# RK3566_DDR3.net
KiCad netlist of a schematic drawn in Altium Designer
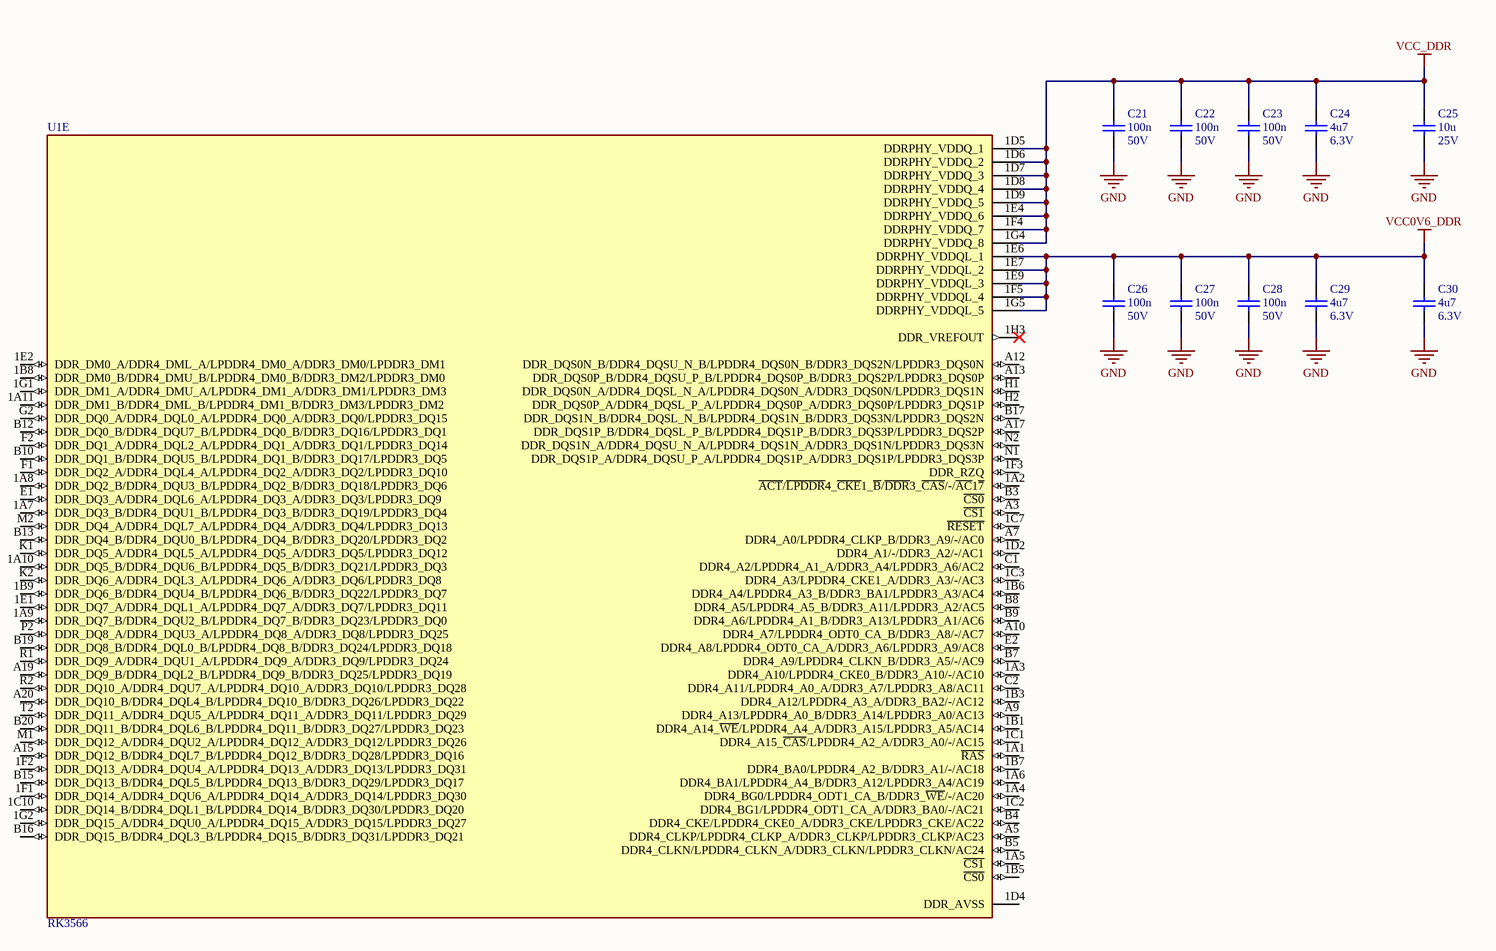
[diagram p0: RK3566_DDR3.SchDoc]

(export (version "E")
  (design (tool "Eeschema 10.0.6"))
  (components
    (comp (ref "C21")
      (value "100n")
      (description "CAP 100N 50V X7R 0402")
      (fields (field (name "VOLTAGE") "50V") (field (name "Comment") "GRM155R71H104KE14D"))
      (libsource (lib "PersonalAltiumLibrary") (part "GRM155R71H104KE14D"))
    )
    (comp (ref "C22")
      (value "100n")
      (description "CAP 100N 50V X7R 0402")
      (fields (field (name "VOLTAGE") "50V") (field (name "Comment") "GRM155R71H104KE14D"))
      (libsource (lib "PersonalAltiumLibrary") (part "GRM155R71H104KE14D"))
    )
    (comp (ref "C23")
      (value "100n")
      (description "CAP 100N 50V X7R 0402")
      (fields (field (name "VOLTAGE") "50V") (field (name "Comment") "GRM155R71H104KE14D"))
      (libsource (lib "PersonalAltiumLibrary") (part "GRM155R71H104KE14D"))
    )
    (comp (ref "C24")
      (value "4u7")
      (description "CAP 4.7U 6.3V X5R 0402")
      (fields (field (name "VOLTAGE") "6.3V") (field (name "Comment") "GRM155R60J475ME47D"))
      (libsource (lib "PersonalAltiumLibrary") (part "GRM155R60J475ME47D"))
    )
    (comp (ref "C25")
      (value "10u")
      (description "CAP 10U 25V X5R 0603")
      (fields (field (name "VOLTAGE") "25V") (field (name "Comment") "GRM188R61E106MA73D"))
      (libsource (lib "PersonalAltiumLibrary") (part "GRM188R61E106MA73D"))
    )
    (comp (ref "C26")
      (value "100n")
      (description "CAP 100N 50V X7R 0402")
      (fields (field (name "VOLTAGE") "50V") (field (name "Comment") "GRM155R71H104KE14D"))
      (libsource (lib "PersonalAltiumLibrary") (part "GRM155R71H104KE14D"))
    )
    (comp (ref "C27")
      (value "100n")
      (description "CAP 100N 50V X7R 0402")
      (fields (field (name "VOLTAGE") "50V") (field (name "Comment") "GRM155R71H104KE14D"))
      (libsource (lib "PersonalAltiumLibrary") (part "GRM155R71H104KE14D"))
    )
    (comp (ref "C28")
      (value "100n")
      (description "CAP 100N 50V X7R 0402")
      (fields (field (name "VOLTAGE") "50V") (field (name "Comment") "GRM155R71H104KE14D"))
      (libsource (lib "PersonalAltiumLibrary") (part "GRM155R71H104KE14D"))
    )
    (comp (ref "C29")
      (value "4u7")
      (description "CAP 4.7U 6.3V X5R 0402")
      (fields (field (name "VOLTAGE") "6.3V") (field (name "Comment") "GRM155R60J475ME47D"))
      (libsource (lib "PersonalAltiumLibrary") (part "GRM155R60J475ME47D"))
    )
    (comp (ref "C30")
      (value "4u7")
      (description "CAP 4.7U 6.3V X5R 0402")
      (fields (field (name "VOLTAGE") "6.3V") (field (name "Comment") "GRM155R60J475ME47D"))
      (libsource (lib "PersonalAltiumLibrary") (part "GRM155R60J475ME47D"))
    )
    (comp (ref "U1")
      (value "RK3566")
      (footprint "RK3566")
      (description "high-performance and low-power quad-core application processor")
      (fields (field (name "MF") "Fuzhou Rockchip Electronics Co"))
      (libsource (lib "PersonalAltiumLibrary") (part "RK3566"))
    )
  )
  (nets
    (net (code "1") (name "GND") (class "Default")
      (node (ref "C21") (pin "2") (pinfunction "2_2") (pintype "passive"))
      (node (ref "C22") (pin "2") (pinfunction "2_2") (pintype "passive"))
      (node (ref "C23") (pin "2") (pinfunction "2_2") (pintype "passive"))
      (node (ref "C24") (pin "2") (pinfunction "2_2") (pintype "passive"))
      (node (ref "C25") (pin "2") (pinfunction "2_2") (pintype "passive"))
      (node (ref "C26") (pin "2") (pinfunction "2_2") (pintype "passive"))
      (node (ref "C27") (pin "2") (pinfunction "2_2") (pintype "passive"))
      (node (ref "C28") (pin "2") (pinfunction "2_2") (pintype "passive"))
      (node (ref "C29") (pin "2") (pinfunction "2_2") (pintype "passive"))
      (node (ref "C30") (pin "2") (pinfunction "2_2") (pintype "passive"))
    )
    (net (code "2") (name "VCC0V6_DDR") (class "Default")
      (node (ref "C26") (pin "1") (pinfunction "1_1") (pintype "passive"))
      (node (ref "C27") (pin "1") (pinfunction "1_1") (pintype "passive"))
      (node (ref "C28") (pin "1") (pinfunction "1_1") (pintype "passive"))
      (node (ref "C29") (pin "1") (pinfunction "1_1") (pintype "passive"))
      (node (ref "C30") (pin "1") (pinfunction "1_1") (pintype "passive"))
      (node (ref "U1") (pin "1E6") (pinfunction "DDRPHY_VDDQL_1_1E6") (pintype "power_in"))
      (node (ref "U1") (pin "1E7") (pinfunction "DDRPHY_VDDQL_2_1E7") (pintype "power_in"))
      (node (ref "U1") (pin "1E9") (pinfunction "DDRPHY_VDDQL_3_1E9") (pintype "power_in"))
      (node (ref "U1") (pin "1F5") (pinfunction "DDRPHY_VDDQL_4_1F5") (pintype "power_in"))
      (node (ref "U1") (pin "1G5") (pinfunction "DDRPHY_VDDQL_5_1G5") (pintype "power_in"))
    )
    (net (code "3") (name "VCC_DDR") (class "Default")
      (node (ref "C21") (pin "1") (pinfunction "1_1") (pintype "passive"))
      (node (ref "C22") (pin "1") (pinfunction "1_1") (pintype "passive"))
      (node (ref "C23") (pin "1") (pinfunction "1_1") (pintype "passive"))
      (node (ref "C24") (pin "1") (pinfunction "1_1") (pintype "passive"))
      (node (ref "C25") (pin "1") (pinfunction "1_1") (pintype "passive"))
      (node (ref "U1") (pin "1D5") (pinfunction "DDRPHY_VDDQ_1_1D5") (pintype "power_in"))
      (node (ref "U1") (pin "1D6") (pinfunction "DDRPHY_VDDQ_2_1D6") (pintype "power_in"))
      (node (ref "U1") (pin "1D7") (pinfunction "DDRPHY_VDDQ_3_1D7") (pintype "power_in"))
      (node (ref "U1") (pin "1D8") (pinfunction "DDRPHY_VDDQ_4_1D8") (pintype "power_in"))
      (node (ref "U1") (pin "1D9") (pinfunction "DDRPHY_VDDQ_5_1D9") (pintype "power_in"))
      (node (ref "U1") (pin "1E4") (pinfunction "DDRPHY_VDDQ_6_1E4") (pintype "power_in"))
      (node (ref "U1") (pin "1F4") (pinfunction "DDRPHY_VDDQ_7_1F4") (pintype "power_in"))
      (node (ref "U1") (pin "1G4") (pinfunction "DDRPHY_VDDQ_8_1G4") (pintype "power_in"))
    )
    (net (code "4") (name "unconnected-(U1E-DDR4_A0{slash}LPDDR4_CLKP_B{slash}DDR3_A9{slash}-{slash}AC0-PadA7)") (class "Default")
      (node (ref "U1") (pin "A7") (pinfunction "DDR4_A0/LPDDR4_CLKP_B/DDR3_A9/-/AC0_A7") (pintype "bidirectional"))
    )
    (net (code "5") (name "unconnected-(U1E-DDR4_A1{slash}-{slash}DDR3_A2{slash}-{slash}AC1-Pad1D2)") (class "Default")
      (node (ref "U1") (pin "1D2") (pinfunction "DDR4_A1/-/DDR3_A2/-/AC1_1D2") (pintype "bidirectional"))
    )
    (net (code "6") (name "unconnected-(U1E-DDR4_A2{slash}LPDDR4_A1_A{slash}DDR3_A4{slash}LPDDR3_A6{slash}AC2-PadC1)") (class "Default")
      (node (ref "U1") (pin "C1") (pinfunction "DDR4_A2/LPDDR4_A1_A/DDR3_A4/LPDDR3_A6/AC2_C1") (pintype "bidirectional"))
    )
    (net (code "7") (name "unconnected-(U1E-DDR4_A3{slash}LPDDR4_CKE1_A{slash}DDR3_A3{slash}-{slash}AC3-Pad1C3)") (class "Default")
      (node (ref "U1") (pin "1C3") (pinfunction "DDR4_A3/LPDDR4_CKE1_A/DDR3_A3/-/AC3_1C3") (pintype "bidirectional"))
    )
    (net (code "8") (name "unconnected-(U1E-DDR4_A4{slash}LPDDR4_A3_B{slash}DDR3_BA1{slash}LPDDR3_A3{slash}AC4-Pad1B6)") (class "Default")
      (node (ref "U1") (pin "1B6") (pinfunction "DDR4_A4/LPDDR4_A3_B/DDR3_BA1/LPDDR3_A3/AC4_1B6") (pintype "bidirectional"))
    )
    (net (code "9") (name "unconnected-(U1E-DDR4_A5{slash}LPDDR4_A5_B{slash}DDR3_A11{slash}LPDDR3_A2{slash}AC5-PadB8)") (class "Default")
      (node (ref "U1") (pin "B8") (pinfunction "DDR4_A5/LPDDR4_A5_B/DDR3_A11/LPDDR3_A2/AC5_B8") (pintype "bidirectional"))
    )
    (net (code "10") (name "unconnected-(U1E-DDR4_A6{slash}LPDDR4_A1_B{slash}DDR3_A13{slash}LPDDR3_A1{slash}AC6-PadB9)") (class "Default")
      (node (ref "U1") (pin "B9") (pinfunction "DDR4_A6/LPDDR4_A1_B/DDR3_A13/LPDDR3_A1/AC6_B9") (pintype "bidirectional"))
    )
    (net (code "11") (name "unconnected-(U1E-DDR4_A7{slash}LPDDR4_ODT0_CA_B{slash}DDR3_A8{slash}-{slash}AC7-PadA10)") (class "Default")
      (node (ref "U1") (pin "A10") (pinfunction "DDR4_A7/LPDDR4_ODT0_CA_B/DDR3_A8/-/AC7_A10") (pintype "bidirectional"))
    )
    (net (code "12") (name "unconnected-(U1E-DDR4_A8{slash}LPDDR4_ODT0_CA_A{slash}DDR3_A6{slash}LPDDR3_A9{slash}AC8-PadE2)") (class "Default")
      (node (ref "U1") (pin "E2") (pinfunction "DDR4_A8/LPDDR4_ODT0_CA_A/DDR3_A6/LPDDR3_A9/AC8_E2") (pintype "bidirectional"))
    )
    (net (code "13") (name "unconnected-(U1E-DDR4_A9{slash}LPDDR4_CLKN_B{slash}DDR3_A5{slash}-{slash}AC9-PadB7)") (class "Default")
      (node (ref "U1") (pin "B7") (pinfunction "DDR4_A9/LPDDR4_CLKN_B/DDR3_A5/-/AC9_B7") (pintype "bidirectional"))
    )
    (net (code "14") (name "unconnected-(U1E-DDR4_A10{slash}LPDDR4_CKE0_B{slash}DDR3_A10{slash}-{slash}AC10-Pad1A3)") (class "Default")
      (node (ref "U1") (pin "1A3") (pinfunction "DDR4_A10/LPDDR4_CKE0_B/DDR3_A10/-/AC10_1A3") (pintype "bidirectional"))
    )
    (net (code "15") (name "unconnected-(U1E-DDR4_A11{slash}LPDDR4_A0_A{slash}DDR3_A7{slash}LPDDR3_A8{slash}AC11-PadC2)") (class "Default")
      (node (ref "U1") (pin "C2") (pinfunction "DDR4_A11/LPDDR4_A0_A/DDR3_A7/LPDDR3_A8/AC11_C2") (pintype "bidirectional"))
    )
    (net (code "16") (name "unconnected-(U1E-DDR4_A12{slash}LPDDR4_A3_A{slash}DDR3_BA2{slash}-{slash}AC12-Pad1B3)") (class "Default")
      (node (ref "U1") (pin "1B3") (pinfunction "DDR4_A12/LPDDR4_A3_A/DDR3_BA2/-/AC12_1B3") (pintype "bidirectional"))
    )
    (net (code "17") (name "unconnected-(U1E-DDR4_A13{slash}LPDDR4_A0_B{slash}DDR3_A14{slash}LPDDR3_A0{slash}AC13-PadA9)") (class "Default")
      (node (ref "U1") (pin "A9") (pinfunction "DDR4_A13/LPDDR4_A0_B/DDR3_A14/LPDDR3_A0/AC13_A9") (pintype "bidirectional"))
    )
    (net (code "18") (name "unconnected-(U1E-DDR4_A14_~{WE}{slash}LPDDR4_A4_A{slash}DDR3_A15{slash}LPDDR3_A5{slash}AC14-Pad1B1)") (class "Default")
      (node (ref "U1") (pin "1B1") (pinfunction "DDR4_A14_~{WE}/LPDDR4_A4_A/DDR3_A15/LPDDR3_A5/AC14_1B1") (pintype "bidirectional"))
    )
    (net (code "19") (name "unconnected-(U1E-DDR4_A15_~{CAS}{slash}LPDDR4_A2_A{slash}DDR3_A0{slash}-{slash}AC15-Pad1C1)") (class "Default")
      (node (ref "U1") (pin "1C1") (pinfunction "DDR4_A15_~{CAS}/LPDDR4_A2_A/DDR3_A0/-/AC15_1C1") (pintype "bidirectional"))
    )
    (net (code "20") (name "unconnected-(U1E-DDR4_BA0{slash}LPDDR4_A2_B{slash}DDR3_A1{slash}-{slash}AC18-Pad1B7)") (class "Default")
      (node (ref "U1") (pin "1B7") (pinfunction "DDR4_BA0/LPDDR4_A2_B/DDR3_A1/-/AC18_1B7") (pintype "bidirectional"))
    )
    (net (code "21") (name "unconnected-(U1E-DDR4_BA1{slash}LPDDR4_A4_B{slash}DDR3_A12{slash}LPDDR3_A4{slash}AC19-Pad1A6)") (class "Default")
      (node (ref "U1") (pin "1A6") (pinfunction "DDR4_BA1/LPDDR4_A4_B/DDR3_A12/LPDDR3_A4/AC19_1A6") (pintype "bidirectional"))
    )
    (net (code "22") (name "unconnected-(U1E-DDR4_BG0{slash}LPDDR4_ODT1_CA_B{slash}DDR3_~{WE}{slash}-{slash}AC20-Pad1A4)") (class "Default")
      (node (ref "U1") (pin "1A4") (pinfunction "DDR4_BG0/LPDDR4_ODT1_CA_B/DDR3_~{WE}/-/AC20_1A4") (pintype "bidirectional"))
    )
    (net (code "23") (name "unconnected-(U1E-DDR4_BG1{slash}LPDDR4_ODT1_CA_A{slash}DDR3_BA0{slash}-{slash}AC21-Pad1C2)") (class "Default")
      (node (ref "U1") (pin "1C2") (pinfunction "DDR4_BG1/LPDDR4_ODT1_CA_A/DDR3_BA0/-/AC21_1C2") (pintype "bidirectional"))
    )
    (net (code "24") (name "unconnected-(U1E-DDR4_CKE{slash}LPDDR4_CKE0_A{slash}DDR3_CKE{slash}LPDDR3_CKE{slash}AC22-PadB4)") (class "Default")
      (node (ref "U1") (pin "B4") (pinfunction "DDR4_CKE/LPDDR4_CKE0_A/DDR3_CKE/LPDDR3_CKE/AC22_B4") (pintype "bidirectional"))
    )
    (net (code "25") (name "unconnected-(U1E-DDR4_CLKN{slash}LPDDR4_CLKN_A{slash}DDR3_CLKN{slash}LPDDR3_CLKN{slash}AC24-PadB5)") (class "Default")
      (node (ref "U1") (pin "B5") (pinfunction "DDR4_CLKN/LPDDR4_CLKN_A/DDR3_CLKN/LPDDR3_CLKN/AC24_B5") (pintype "bidirectional"))
    )
    (net (code "26") (name "unconnected-(U1E-DDR4_CLKP{slash}LPDDR4_CLKP_A{slash}DDR3_CLKP{slash}LPDDR3_CLKP{slash}AC23-PadA5)") (class "Default")
      (node (ref "U1") (pin "A5") (pinfunction "DDR4_CLKP/LPDDR4_CLKP_A/DDR3_CLKP/LPDDR3_CLKP/AC23_A5") (pintype "bidirectional"))
    )
    (net (code "27") (name "unconnected-(U1E-DDR_AVSS-Pad1D4)") (class "Default")
      (node (ref "U1") (pin "1D4") (pinfunction "DDR_AVSS_1D4") (pintype "power_in"))
    )
    (net (code "28") (name "unconnected-(U1E-DDR_DM0_A{slash}DDR4_DML_A{slash}LPDDR4_DM0_A{slash}DDR3_DM0{slash}LPDDR3_DM1-Pad1E2)") (class "Default")
      (node (ref "U1") (pin "1E2") (pinfunction "DDR_DM0_A/DDR4_DML_A/LPDDR4_DM0_A/DDR3_DM0/LPDDR3_DM1_1E2") (pintype "bidirectional"))
    )
    (net (code "29") (name "unconnected-(U1E-DDR_DM0_B{slash}DDR4_DMU_B{slash}LPDDR4_DM0_B{slash}DDR3_DM2{slash}LPDDR3_DM0-Pad1B8)") (class "Default")
      (node (ref "U1") (pin "1B8") (pinfunction "DDR_DM0_B/DDR4_DMU_B/LPDDR4_DM0_B/DDR3_DM2/LPDDR3_DM0_1B8") (pintype "bidirectional"))
    )
    (net (code "30") (name "unconnected-(U1E-DDR_DM1_A{slash}DDR4_DMU_A{slash}LPDDR4_DM1_A{slash}DDR3_DM1{slash}LPDDR3_DM3-Pad1G1)") (class "Default")
      (node (ref "U1") (pin "1G1") (pinfunction "DDR_DM1_A/DDR4_DMU_A/LPDDR4_DM1_A/DDR3_DM1/LPDDR3_DM3_1G1") (pintype "bidirectional"))
    )
    (net (code "31") (name "unconnected-(U1E-DDR_DM1_B{slash}DDR4_DML_B{slash}LPDDR4_DM1_B{slash}DDR3_DM3{slash}LPDDR3_DM2-Pad1A11)") (class "Default")
      (node (ref "U1") (pin "1A11") (pinfunction "DDR_DM1_B/DDR4_DML_B/LPDDR4_DM1_B/DDR3_DM3/LPDDR3_DM2_1A11") (pintype "bidirectional"))
    )
    (net (code "32") (name "unconnected-(U1E-DDR_DQ0_A{slash}DDR4_DQL0_A{slash}LPDDR4_DQ0_A{slash}DDR3_DQ0{slash}LPDDR3_DQ15-PadG2)") (class "Default")
      (node (ref "U1") (pin "G2") (pinfunction "DDR_DQ0_A/DDR4_DQL0_A/LPDDR4_DQ0_A/DDR3_DQ0/LPDDR3_DQ15_G2") (pintype "bidirectional"))
    )
    (net (code "33") (name "unconnected-(U1E-DDR_DQ0_B{slash}DDR4_DQU7_B{slash}LPDDR4_DQ0_B{slash}DDR3_DQ16{slash}LPDDR3_DQ1-PadB12)") (class "Default")
      (node (ref "U1") (pin "B12") (pinfunction "DDR_DQ0_B/DDR4_DQU7_B/LPDDR4_DQ0_B/DDR3_DQ16/LPDDR3_DQ1_B12") (pintype "bidirectional"))
    )
    (net (code "34") (name "unconnected-(U1E-DDR_DQ1_A{slash}DDR4_DQL2_A{slash}LPDDR4_DQ1_A{slash}DDR3_DQ1{slash}LPDDR3_DQ14-PadF2)") (class "Default")
      (node (ref "U1") (pin "F2") (pinfunction "DDR_DQ1_A/DDR4_DQL2_A/LPDDR4_DQ1_A/DDR3_DQ1/LPDDR3_DQ14_F2") (pintype "bidirectional"))
    )
    (net (code "35") (name "unconnected-(U1E-DDR_DQ1_B{slash}DDR4_DQU5_B{slash}LPDDR4_DQ1_B{slash}DDR3_DQ17{slash}LPDDR3_DQ5-PadB10)") (class "Default")
      (node (ref "U1") (pin "B10") (pinfunction "DDR_DQ1_B/DDR4_DQU5_B/LPDDR4_DQ1_B/DDR3_DQ17/LPDDR3_DQ5_B10") (pintype "bidirectional"))
    )
    (net (code "36") (name "unconnected-(U1E-DDR_DQ2_A{slash}DDR4_DQL4_A{slash}LPDDR4_DQ2_A{slash}DDR3_DQ2{slash}LPDDR3_DQ10-PadF1)") (class "Default")
      (node (ref "U1") (pin "F1") (pinfunction "DDR_DQ2_A/DDR4_DQL4_A/LPDDR4_DQ2_A/DDR3_DQ2/LPDDR3_DQ10_F1") (pintype "bidirectional"))
    )
    (net (code "37") (name "unconnected-(U1E-DDR_DQ2_B{slash}DDR4_DQU3_B{slash}LPDDR4_DQ2_B{slash}DDR3_DQ18{slash}LPDDR3_DQ6-Pad1A8)") (class "Default")
      (node (ref "U1") (pin "1A8") (pinfunction "DDR_DQ2_B/DDR4_DQU3_B/LPDDR4_DQ2_B/DDR3_DQ18/LPDDR3_DQ6_1A8") (pintype "bidirectional"))
    )
    (net (code "38") (name "unconnected-(U1E-DDR_DQ3_A{slash}DDR4_DQL6_A{slash}LPDDR4_DQ3_A{slash}DDR3_DQ3{slash}LPDDR3_DQ9-PadE1)") (class "Default")
      (node (ref "U1") (pin "E1") (pinfunction "DDR_DQ3_A/DDR4_DQL6_A/LPDDR4_DQ3_A/DDR3_DQ3/LPDDR3_DQ9_E1") (pintype "bidirectional"))
    )
    (net (code "39") (name "unconnected-(U1E-DDR_DQ3_B{slash}DDR4_DQU1_B{slash}LPDDR4_DQ3_B{slash}DDR3_DQ19{slash}LPDDR3_DQ4-Pad1A7)") (class "Default")
      (node (ref "U1") (pin "1A7") (pinfunction "DDR_DQ3_B/DDR4_DQU1_B/LPDDR4_DQ3_B/DDR3_DQ19/LPDDR3_DQ4_1A7") (pintype "bidirectional"))
    )
    (net (code "40") (name "unconnected-(U1E-DDR_DQ4_A{slash}DDR4_DQL7_A{slash}LPDDR4_DQ4_A{slash}DDR3_DQ4{slash}LPDDR3_DQ13-PadM2)") (class "Default")
      (node (ref "U1") (pin "M2") (pinfunction "DDR_DQ4_A/DDR4_DQL7_A/LPDDR4_DQ4_A/DDR3_DQ4/LPDDR3_DQ13_M2") (pintype "bidirectional"))
    )
    (net (code "41") (name "unconnected-(U1E-DDR_DQ4_B{slash}DDR4_DQU0_B{slash}LPDDR4_DQ4_B{slash}DDR3_DQ20{slash}LPDDR3_DQ2-PadB13)") (class "Default")
      (node (ref "U1") (pin "B13") (pinfunction "DDR_DQ4_B/DDR4_DQU0_B/LPDDR4_DQ4_B/DDR3_DQ20/LPDDR3_DQ2_B13") (pintype "bidirectional"))
    )
    (net (code "42") (name "unconnected-(U1E-DDR_DQ5_A{slash}DDR4_DQL5_A{slash}LPDDR4_DQ5_A{slash}DDR3_DQ5{slash}LPDDR3_DQ12-PadK1)") (class "Default")
      (node (ref "U1") (pin "K1") (pinfunction "DDR_DQ5_A/DDR4_DQL5_A/LPDDR4_DQ5_A/DDR3_DQ5/LPDDR3_DQ12_K1") (pintype "bidirectional"))
    )
    (net (code "43") (name "unconnected-(U1E-DDR_DQ5_B{slash}DDR4_DQU6_B{slash}LPDDR4_DQ5_B{slash}DDR3_DQ21{slash}LPDDR3_DQ3-Pad1A10)") (class "Default")
      (node (ref "U1") (pin "1A10") (pinfunction "DDR_DQ5_B/DDR4_DQU6_B/LPDDR4_DQ5_B/DDR3_DQ21/LPDDR3_DQ3_1A10") (pintype "bidirectional"))
    )
    (net (code "44") (name "unconnected-(U1E-DDR_DQ6_A{slash}DDR4_DQL3_A{slash}LPDDR4_DQ6_A{slash}DDR3_DQ6{slash}LPDDR3_DQ8-PadK2)") (class "Default")
      (node (ref "U1") (pin "K2") (pinfunction "DDR_DQ6_A/DDR4_DQL3_A/LPDDR4_DQ6_A/DDR3_DQ6/LPDDR3_DQ8_K2") (pintype "bidirectional"))
    )
    (net (code "45") (name "unconnected-(U1E-DDR_DQ6_B{slash}DDR4_DQU4_B{slash}LPDDR4_DQ6_B{slash}DDR3_DQ22{slash}LPDDR3_DQ7-Pad1B9)") (class "Default")
      (node (ref "U1") (pin "1B9") (pinfunction "DDR_DQ6_B/DDR4_DQU4_B/LPDDR4_DQ6_B/DDR3_DQ22/LPDDR3_DQ7_1B9") (pintype "bidirectional"))
    )
    (net (code "46") (name "unconnected-(U1E-DDR_DQ7_A{slash}DDR4_DQL1_A{slash}LPDDR4_DQ7_A{slash}DDR3_DQ7{slash}LPDDR3_DQ11-Pad1E1)") (class "Default")
      (node (ref "U1") (pin "1E1") (pinfunction "DDR_DQ7_A/DDR4_DQL1_A/LPDDR4_DQ7_A/DDR3_DQ7/LPDDR3_DQ11_1E1") (pintype "bidirectional"))
    )
    (net (code "47") (name "unconnected-(U1E-DDR_DQ7_B{slash}DDR4_DQU2_B{slash}LPDDR4_DQ7_B{slash}DDR3_DQ23{slash}LPDDR3_DQ0-Pad1A9)") (class "Default")
      (node (ref "U1") (pin "1A9") (pinfunction "DDR_DQ7_B/DDR4_DQU2_B/LPDDR4_DQ7_B/DDR3_DQ23/LPDDR3_DQ0_1A9") (pintype "bidirectional"))
    )
    (net (code "48") (name "unconnected-(U1E-DDR_DQ8_A{slash}DDR4_DQU3_A{slash}LPDDR4_DQ8_A{slash}DDR3_DQ8{slash}LPDDR3_DQ25-PadP2)") (class "Default")
      (node (ref "U1") (pin "P2") (pinfunction "DDR_DQ8_A/DDR4_DQU3_A/LPDDR4_DQ8_A/DDR3_DQ8/LPDDR3_DQ25_P2") (pintype "bidirectional"))
    )
    (net (code "49") (name "unconnected-(U1E-DDR_DQ8_B{slash}DDR4_DQL0_B{slash}LPDDR4_DQ8_B{slash}DDR3_DQ24{slash}LPDDR3_DQ18-PadB19)") (class "Default")
      (node (ref "U1") (pin "B19") (pinfunction "DDR_DQ8_B/DDR4_DQL0_B/LPDDR4_DQ8_B/DDR3_DQ24/LPDDR3_DQ18_B19") (pintype "bidirectional"))
    )
    (net (code "50") (name "unconnected-(U1E-DDR_DQ9_A{slash}DDR4_DQU1_A{slash}LPDDR4_DQ9_A{slash}DDR3_DQ9{slash}LPDDR3_DQ24-PadR1)") (class "Default")
      (node (ref "U1") (pin "R1") (pinfunction "DDR_DQ9_A/DDR4_DQU1_A/LPDDR4_DQ9_A/DDR3_DQ9/LPDDR3_DQ24_R1") (pintype "bidirectional"))
    )
    (net (code "51") (name "unconnected-(U1E-DDR_DQ9_B{slash}DDR4_DQL2_B{slash}LPDDR4_DQ9_B{slash}DDR3_DQ25{slash}LPDDR3_DQ19-PadA19)") (class "Default")
      (node (ref "U1") (pin "A19") (pinfunction "DDR_DQ9_B/DDR4_DQL2_B/LPDDR4_DQ9_B/DDR3_DQ25/LPDDR3_DQ19_A19") (pintype "bidirectional"))
    )
    (net (code "52") (name "unconnected-(U1E-DDR_DQ10_A{slash}DDR4_DQU7_A{slash}LPDDR4_DQ10_A{slash}DDR3_DQ10{slash}LPDDR3_DQ28-PadR2)") (class "Default")
      (node (ref "U1") (pin "R2") (pinfunction "DDR_DQ10_A/DDR4_DQU7_A/LPDDR4_DQ10_A/DDR3_DQ10/LPDDR3_DQ28_R2") (pintype "bidirectional"))
    )
    (net (code "53") (name "unconnected-(U1E-DDR_DQ10_B{slash}DDR4_DQL4_B{slash}LPDDR4_DQ10_B{slash}DDR3_DQ26{slash}LPDDR3_DQ22-PadA20)") (class "Default")
      (node (ref "U1") (pin "A20") (pinfunction "DDR_DQ10_B/DDR4_DQL4_B/LPDDR4_DQ10_B/DDR3_DQ26/LPDDR3_DQ22_A20") (pintype "bidirectional"))
    )
    (net (code "54") (name "unconnected-(U1E-DDR_DQ11_A{slash}DDR4_DQU5_A{slash}LPDDR4_DQ11_A{slash}DDR3_DQ11{slash}LPDDR3_DQ29-PadT2)") (class "Default")
      (node (ref "U1") (pin "T2") (pinfunction "DDR_DQ11_A/DDR4_DQU5_A/LPDDR4_DQ11_A/DDR3_DQ11/LPDDR3_DQ29_T2") (pintype "bidirectional"))
    )
    (net (code "55") (name "unconnected-(U1E-DDR_DQ11_B{slash}DDR4_DQL6_B{slash}LPDDR4_DQ11_B{slash}DDR3_DQ27{slash}LPDDR3_DQ23-PadB20)") (class "Default")
      (node (ref "U1") (pin "B20") (pinfunction "DDR_DQ11_B/DDR4_DQL6_B/LPDDR4_DQ11_B/DDR3_DQ27/LPDDR3_DQ23_B20") (pintype "bidirectional"))
    )
    (net (code "56") (name "unconnected-(U1E-DDR_DQ12_A{slash}DDR4_DQU2_A{slash}LPDDR4_DQ12_A{slash}DDR3_DQ12{slash}LPDDR3_DQ26-PadM1)") (class "Default")
      (node (ref "U1") (pin "M1") (pinfunction "DDR_DQ12_A/DDR4_DQU2_A/LPDDR4_DQ12_A/DDR3_DQ12/LPDDR3_DQ26_M1") (pintype "bidirectional"))
    )
    (net (code "57") (name "unconnected-(U1E-DDR_DQ12_B{slash}DDR4_DQL7_B{slash}LPDDR4_DQ12_B{slash}DDR3_DQ28{slash}LPDDR3_DQ16-PadA15)") (class "Default")
      (node (ref "U1") (pin "A15") (pinfunction "DDR_DQ12_B/DDR4_DQL7_B/LPDDR4_DQ12_B/DDR3_DQ28/LPDDR3_DQ16_A15") (pintype "bidirectional"))
    )
    (net (code "58") (name "unconnected-(U1E-DDR_DQ13_A{slash}DDR4_DQU4_A{slash}LPDDR4_DQ13_A{slash}DDR3_DQ13{slash}LPDDR3_DQ31-Pad1F2)") (class "Default")
      (node (ref "U1") (pin "1F2") (pinfunction "DDR_DQ13_A/DDR4_DQU4_A/LPDDR4_DQ13_A/DDR3_DQ13/LPDDR3_DQ31_1F2") (pintype "bidirectional"))
    )
    (net (code "59") (name "unconnected-(U1E-DDR_DQ13_B{slash}DDR4_DQL5_B{slash}LPDDR4_DQ13_B{slash}DDR3_DQ29{slash}LPDDR3_DQ17-PadB15)") (class "Default")
      (node (ref "U1") (pin "B15") (pinfunction "DDR_DQ13_B/DDR4_DQL5_B/LPDDR4_DQ13_B/DDR3_DQ29/LPDDR3_DQ17_B15") (pintype "bidirectional"))
    )
    (net (code "60") (name "unconnected-(U1E-DDR_DQ14_A{slash}DDR4_DQU6_A{slash}LPDDR4_DQ14_A{slash}DDR3_DQ14{slash}LPDDR3_DQ30-Pad1F1)") (class "Default")
      (node (ref "U1") (pin "1F1") (pinfunction "DDR_DQ14_A/DDR4_DQU6_A/LPDDR4_DQ14_A/DDR3_DQ14/LPDDR3_DQ30_1F1") (pintype "bidirectional"))
    )
    (net (code "61") (name "unconnected-(U1E-DDR_DQ14_B{slash}DDR4_DQL1_B{slash}LPDDR4_DQ14_B{slash}DDR3_DQ30{slash}LPDDR3_DQ20-Pad1C10)") (class "Default")
      (node (ref "U1") (pin "1C10") (pinfunction "DDR_DQ14_B/DDR4_DQL1_B/LPDDR4_DQ14_B/DDR3_DQ30/LPDDR3_DQ20_1C10") (pintype "bidirectional"))
    )
    (net (code "62") (name "unconnected-(U1E-DDR_DQ15_A{slash}DDR4_DQU0_A{slash}LPDDR4_DQ15_A{slash}DDR3_DQ15{slash}LPDDR3_DQ27-Pad1G2)") (class "Default")
      (node (ref "U1") (pin "1G2") (pinfunction "DDR_DQ15_A/DDR4_DQU0_A/LPDDR4_DQ15_A/DDR3_DQ15/LPDDR3_DQ27_1G2") (pintype "bidirectional"))
    )
    (net (code "63") (name "unconnected-(U1E-DDR_DQ15_B{slash}DDR4_DQL3_B{slash}LPDDR4_DQ15_B{slash}DDR3_DQ31{slash}LPDDR3_DQ21-PadB16)") (class "Default")
      (node (ref "U1") (pin "B16") (pinfunction "DDR_DQ15_B/DDR4_DQL3_B/LPDDR4_DQ15_B/DDR3_DQ31/LPDDR3_DQ21_B16") (pintype "bidirectional"))
    )
    (net (code "64") (name "unconnected-(U1E-DDR_DQS0N_A{slash}DDR4_DQSL_N_A{slash}LPDDR4_DQS0N_A{slash}DDR3_DQS0N{slash}LPDDR3_DQS1N-PadH1)") (class "Default")
      (node (ref "U1") (pin "H1") (pinfunction "DDR_DQS0N_A/DDR4_DQSL_N_A/LPDDR4_DQS0N_A/DDR3_DQS0N/LPDDR3_DQS1N_H1") (pintype "bidirectional"))
    )
    (net (code "65") (name "unconnected-(U1E-DDR_DQS0N_B{slash}DDR4_DQSU_N_B{slash}LPDDR4_DQS0N_B{slash}DDR3_DQS2N{slash}LPDDR3_DQS0N-PadA12)") (class "Default")
      (node (ref "U1") (pin "A12") (pinfunction "DDR_DQS0N_B/DDR4_DQSU_N_B/LPDDR4_DQS0N_B/DDR3_DQS2N/LPDDR3_DQS0N_A12") (pintype "bidirectional"))
    )
    (net (code "66") (name "unconnected-(U1E-DDR_DQS0P_A{slash}DDR4_DQSL_P_A{slash}LPDDR4_DQS0P_A{slash}DDR3_DQS0P{slash}LPDDR3_DQS1P-PadH2)") (class "Default")
      (node (ref "U1") (pin "H2") (pinfunction "DDR_DQS0P_A/DDR4_DQSL_P_A/LPDDR4_DQS0P_A/DDR3_DQS0P/LPDDR3_DQS1P_H2") (pintype "bidirectional"))
    )
    (net (code "67") (name "unconnected-(U1E-DDR_DQS0P_B{slash}DDR4_DQSU_P_B{slash}LPDDR4_DQS0P_B{slash}DDR3_DQS2P{slash}LPDDR3_DQS0P-PadA13)") (class "Default")
      (node (ref "U1") (pin "A13") (pinfunction "DDR_DQS0P_B/DDR4_DQSU_P_B/LPDDR4_DQS0P_B/DDR3_DQS2P/LPDDR3_DQS0P_A13") (pintype "bidirectional"))
    )
    (net (code "68") (name "unconnected-(U1E-DDR_DQS1N_A{slash}DDR4_DQSU_N_A{slash}LPDDR4_DQS1N_A{slash}DDR3_DQS1N{slash}LPDDR3_DQS3N-PadN2)") (class "Default")
      (node (ref "U1") (pin "N2") (pinfunction "DDR_DQS1N_A/DDR4_DQSU_N_A/LPDDR4_DQS1N_A/DDR3_DQS1N/LPDDR3_DQS3N_N2") (pintype "bidirectional"))
    )
    (net (code "69") (name "unconnected-(U1E-DDR_DQS1N_B{slash}DDR4_DQSL_N_B{slash}LPDDR4_DQS1N_B{slash}DDR3_DQS3N{slash}LPDDR3_DQS2N-PadB17)") (class "Default")
      (node (ref "U1") (pin "B17") (pinfunction "DDR_DQS1N_B/DDR4_DQSL_N_B/LPDDR4_DQS1N_B/DDR3_DQS3N/LPDDR3_DQS2N_B17") (pintype "bidirectional"))
    )
    (net (code "70") (name "unconnected-(U1E-DDR_DQS1P_A{slash}DDR4_DQSU_P_A{slash}LPDDR4_DQS1P_A{slash}DDR3_DQS1P{slash}LPDDR3_DQS3P-PadN1)") (class "Default")
      (node (ref "U1") (pin "N1") (pinfunction "DDR_DQS1P_A/DDR4_DQSU_P_A/LPDDR4_DQS1P_A/DDR3_DQS1P/LPDDR3_DQS3P_N1") (pintype "bidirectional"))
    )
    (net (code "71") (name "unconnected-(U1E-DDR_DQS1P_B{slash}DDR4_DQSL_P_B{slash}LPDDR4_DQS1P_B{slash}DDR3_DQS3P{slash}LPDDR3_DQS2P-PadA17)") (class "Default")
      (node (ref "U1") (pin "A17") (pinfunction "DDR_DQS1P_B/DDR4_DQSL_P_B/LPDDR4_DQS1P_B/DDR3_DQS3P/LPDDR3_DQS2P_A17") (pintype "bidirectional"))
    )
    (net (code "72") (name "unconnected-(U1E-DDR_RZQ-Pad1F3)") (class "Default")
      (node (ref "U1") (pin "1F3") (pinfunction "DDR_RZQ_1F3") (pintype "bidirectional"))
    )
    (net (code "73") (name "unconnected-(U1E-DDR_VREFOUT-Pad1H3)") (class "Default")
      (node (ref "U1") (pin "1H3") (pinfunction "DDR_VREFOUT_1H3") (pintype "output+no_connect"))
    )
    (net (code "74") (name "unconnected-(U1E-~{ACT}{slash}~{LPDDR}4_~{CKE}1_~{B}{slash}~{DDR}3_~{CAS}{slash}-{slash}~{AC}1~{7}-Pad1A2)") (class "Default")
      (node (ref "U1") (pin "1A2") (pinfunction "~{ACT}/~{LPDDR}4_~{CKE}1_~{B}/~{DDR}3_~{CAS}/-/~{AC}1~{7}_1A2") (pintype "bidirectional"))
    )
    (net (code "75") (name "unconnected-(U1E-~{CS0}-Pad1B5)") (class "Default")
      (node (ref "U1") (pin "1B5") (pinfunction "~{CS0}_1B5") (pintype "bidirectional"))
    )
    (net (code "76") (name "unconnected-(U1E-~{CS0}-PadB3)") (class "Default")
      (node (ref "U1") (pin "B3") (pinfunction "~{CS0}_B3") (pintype "bidirectional"))
    )
    (net (code "77") (name "unconnected-(U1E-~{CS1}-Pad1A5)") (class "Default")
      (node (ref "U1") (pin "1A5") (pinfunction "~{CS1}_1A5") (pintype "bidirectional"))
    )
    (net (code "78") (name "unconnected-(U1E-~{CS1}-PadA3)") (class "Default")
      (node (ref "U1") (pin "A3") (pinfunction "~{CS1}_A3") (pintype "bidirectional"))
    )
    (net (code "79") (name "unconnected-(U1E-~{RAS}-Pad1A1)") (class "Default")
      (node (ref "U1") (pin "1A1") (pinfunction "~{RAS}_1A1") (pintype "bidirectional"))
    )
    (net (code "80") (name "unconnected-(U1E-~{RESET}-Pad1C7)") (class "Default")
      (node (ref "U1") (pin "1C7") (pinfunction "~{RESET}_1C7") (pintype "bidirectional"))
    )
  )
)
